# SSR_Ctrol.net
KiCad netlist of a schematic drawn in Altium Designer
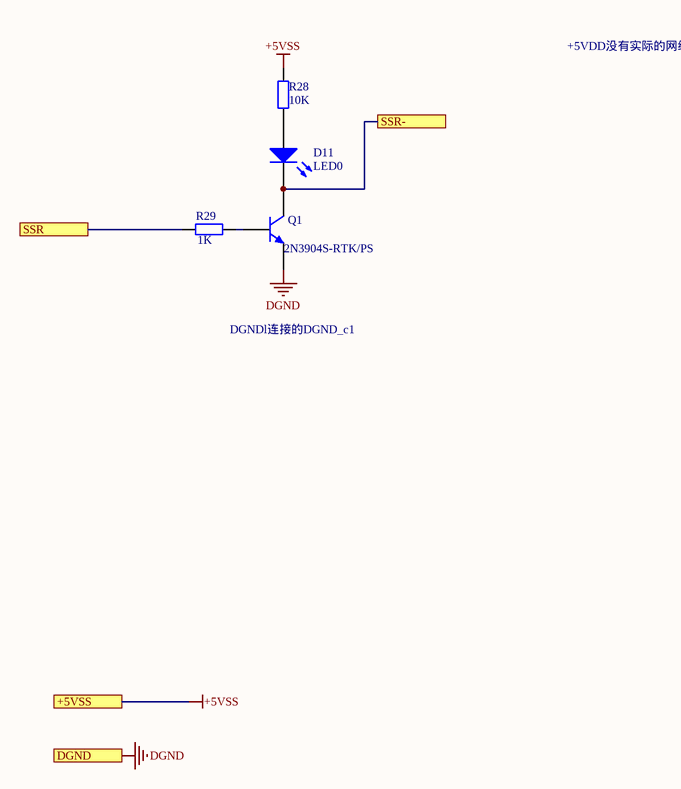
[diagram p0: SSR_Ctrol.SchDoc]

(export (version "E")
  (design (tool "Eeschema 10.0.6"))
  (components
    (comp (ref "D11")
      (value "LED0")
      (footprint "0805LED")
      (description "品牌： 国星光电 型号： NCD0805B2 发光颜色：蓝灯 贴片LED；0805蓝色；2012蓝色；透镜颜色：无色透明；发光角度：130°；功率：72mW；工作温度：-30℃~+85℃；")
      (fields (field (name "PUBLISHER") "Altium Limited"))
      (libsource (lib "Miscellaneous Devices") (part "LED0"))
    )
    (comp (ref "Q1")
      (value "2N3904S-RTK/PS")
      (footprint "SOT-23")
      (fields (field (name "PUBLISHER") "Altium Limited"))
      (libsource (lib "Miscellaneous Devices") (part "2N3904"))
    )
    (comp (ref "R28")
      (value "10K")
      (footprint "0805R")
      (description "品牌： UNI-ROYAL(厚声) 型号： 0805W8F1002T5E 电阻类型：厚膜电阻 阻值：10kΩ 精度：±1% 功率：125mW 温度系数：±100ppm/℃")
      (fields (field (name "PUBLISHER") "Altium Limited"))
      (libsource (lib "Miscellaneous Devices") (part "Res2"))
    )
    (comp (ref "R29")
      (value "1K")
      (footprint "0805R")
      (description "品牌： UNI-ROYAL(厚声) 型号： 0805W8F1001T5E 电阻类型：厚膜电阻 阻值：1kΩ 精度：±1% 功率：125mW 温度系数：±100ppm/℃")
      (fields (field (name "PUBLISHER") "Altium Limited"))
      (libsource (lib "") (part "Res2_1"))
    )
  )
  (nets
    (net (code "1") (name "+5VSS") (class "Default")
      (node (ref "R28") (pin "2") (pinfunction "2_2") (pintype "passive"))
    )
    (net (code "2") (name "/SSR") (class "Default")
      (node (ref "R29") (pin "1") (pinfunction "1_1") (pintype "passive"))
    )
    (net (code "3") (name "/SSR-") (class "Default")
      (node (ref "D11") (pin "2") (pinfunction "K_2") (pintype "passive"))
      (node (ref "Q1") (pin "3") (pinfunction "C_3") (pintype "passive"))
    )
    (net (code "4") (name "DGND") (class "Default")
      (node (ref "Q1") (pin "2") (pinfunction "E_2") (pintype "passive"))
    )
    (net (code "5") (name "Net-(D11-A)") (class "Default")
      (node (ref "D11") (pin "1") (pinfunction "A_1") (pintype "passive"))
      (node (ref "R28") (pin "1") (pinfunction "1_1") (pintype "passive"))
    )
    (net (code "6") (name "Net-(Q1-B)") (class "Default")
      (node (ref "Q1") (pin "1") (pinfunction "B_1") (pintype "passive"))
      (node (ref "R29") (pin "2") (pinfunction "2_2") (pintype "passive"))
    )
  )
)
